# test_device_edit.net
KiCad netlist of a schematic drawn in EAGLE
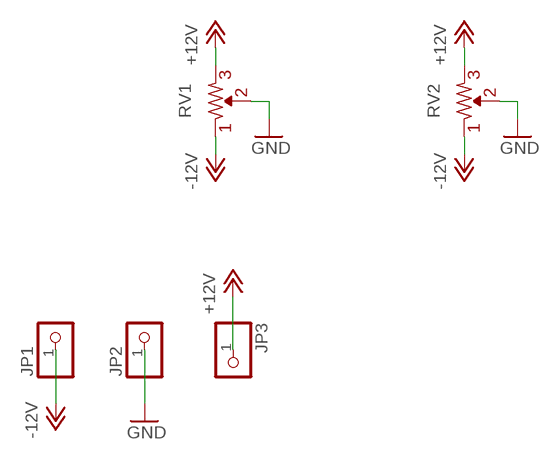
[diagram p0: schematic, sheet 1]

(export (version "E")
  (design (tool "Eeschema 10.0.6"))
  (components
    (comp (ref "JP1")
      (value "PINHD-1X1")
      (footprint "eagle-import:1X01")
      (libsource (lib "eagle-import") (part "PINHD-1X1"))
    )
    (comp (ref "JP2")
      (value "PINHD-1X1")
      (footprint "eagle-import:1X01")
      (libsource (lib "eagle-import") (part "PINHD-1X1"))
    )
    (comp (ref "JP3")
      (value "PINHD-1X1")
      (footprint "eagle-import:1X01")
      (libsource (lib "eagle-import") (part "PINHD-1X1"))
    )
    (comp (ref "RV1")
      (value "R-VAR")
      (footprint "eagle-import:R-VAR")
      (libsource (lib "eagle-import") (part "R-VAR"))
    )
    (comp (ref "RV2")
      (value "R-VARR-VAR-10")
      (footprint "eagle-import:_COMMON_3RP_1610N")
      (libsource (lib "eagle-import") (part "R-VARR-VAR-10"))
    )
  )
  (nets
    (net (code "1") (name "+12V") (class "Default")
      (node (ref "JP3") (pin "1") (pinfunction "1_1") (pintype "passive"))
      (node (ref "RV1") (pin "R2") (pinfunction "3_R2") (pintype "passive"))
      (node (ref "RV2") (pin "3") (pinfunction "3_3") (pintype "passive"))
    )
    (net (code "2") (name "-12V") (class "Default")
      (node (ref "JP1") (pin "1") (pinfunction "1_1") (pintype "passive"))
      (node (ref "RV1") (pin "R1") (pinfunction "1_R1") (pintype "passive"))
      (node (ref "RV2") (pin "1") (pinfunction "1_1") (pintype "passive"))
    )
    (net (code "3") (name "GND") (class "Default")
      (node (ref "JP2") (pin "1") (pinfunction "1_1") (pintype "passive"))
      (node (ref "RV1") (pin "VAR") (pinfunction "2_VAR") (pintype "passive"))
      (node (ref "RV2") (pin "2") (pinfunction "2_2") (pintype "passive"))
    )
  )
)
